# Power.net
KiCad netlist of a schematic drawn in Altium Designer
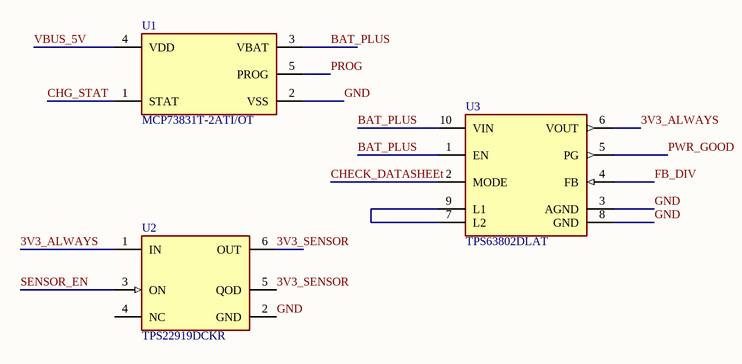
[diagram p0: Power.SchDoc]

(export (version "E")
  (design (tool "Eeschema 10.0.6"))
  (components
    (comp (ref "U1")
      (value "MCP73831T-2ATI/OT")
      (footprint "FP-C04-091-OT-IPC_C")
      (description "IC CONTROLLR LI-ION 4.2V SOT23-5")
      (libsource (lib "Altium Content Vault") (part "a15496f3f0dd9906c1bee5f8dba5d2c"))
    )
    (comp (ref "U2")
      (value "TPS22919DCKR")
      (footprint "FP-DCK0006A-MFG")
      (description "POWER MANAGEMENT")
      (libsource (lib "Altium Content Vault") (part "7dede5ae6ec4f64f362f8612ed9bb45"))
    )
    (comp (ref "U3")
      (value "TPS63802DLAT")
      (footprint "FP-DLA0010A-MFG")
      (description "IC POWER MANAGEMENT")
      (libsource (lib "Altium Content Vault") (part "8d45d195b7242b3c2df1455821f2d89"))
    )
  )
  (nets
    (net (code "1") (name "/3V3_ALWAYS") (class "Default")
      (node (ref "U2") (pin "1") (pinfunction "IN_1") (pintype "power_in"))
      (node (ref "U3") (pin "6") (pinfunction "VOUT_6") (pintype "output"))
    )
    (net (code "2") (name "/3V3_SENSOR") (class "Default")
      (node (ref "U2") (pin "5") (pinfunction "QOD_5") (pintype "passive"))
      (node (ref "U2") (pin "6") (pinfunction "OUT_6") (pintype "power_in"))
    )
    (net (code "3") (name "/BAT_PLUS") (class "Default")
      (node (ref "U1") (pin "3") (pinfunction "VBAT_3") (pintype "power_in"))
      (node (ref "U3") (pin "1") (pinfunction "EN_1") (pintype "passive"))
      (node (ref "U3") (pin "10") (pinfunction "VIN_10") (pintype "power_in"))
    )
    (net (code "4") (name "/CHECK_DATASHEEt") (class "Default")
      (node (ref "U3") (pin "2") (pinfunction "MODE_2") (pintype "passive"))
    )
    (net (code "5") (name "/CHG_STAT") (class "Default")
      (node (ref "U1") (pin "1") (pinfunction "STAT_1") (pintype "passive"))
    )
    (net (code "6") (name "/FB_DIV") (class "Default")
      (node (ref "U3") (pin "4") (pinfunction "FB_4") (pintype "input"))
    )
    (net (code "7") (name "/GND") (class "Default")
      (node (ref "U1") (pin "2") (pinfunction "VSS_2") (pintype "power_in"))
      (node (ref "U2") (pin "2") (pinfunction "GND_2") (pintype "power_in"))
      (node (ref "U3") (pin "3") (pinfunction "AGND_3") (pintype "power_in"))
      (node (ref "U3") (pin "8") (pinfunction "GND_8") (pintype "power_in"))
    )
    (net (code "8") (name "/PROG") (class "Default")
      (node (ref "U1") (pin "5") (pinfunction "PROG_5") (pintype "passive"))
    )
    (net (code "9") (name "/PWR_GOOD") (class "Default")
      (node (ref "U3") (pin "5") (pinfunction "PG_5") (pintype "output"))
    )
    (net (code "10") (name "/SENSOR_EN") (class "Default")
      (node (ref "U2") (pin "3") (pinfunction "ON_3") (pintype "input"))
    )
    (net (code "11") (name "/VBUS_5V") (class "Default")
      (node (ref "U1") (pin "4") (pinfunction "VDD_4") (pintype "power_in"))
    )
    (net (code "12") (name "Net-(U3-L1)") (class "Default")
      (node (ref "U3") (pin "7") (pinfunction "L2_7") (pintype "passive"))
      (node (ref "U3") (pin "9") (pinfunction "L1_9") (pintype "passive"))
    )
    (net (code "13") (name "unconnected-(U2-NC-Pad4)") (class "Default")
      (node (ref "U2") (pin "4") (pinfunction "NC_4") (pintype "passive"))
    )
  )
)
